# PC-FX.net
KiCad netlist of a schematic drawn in EAGLE
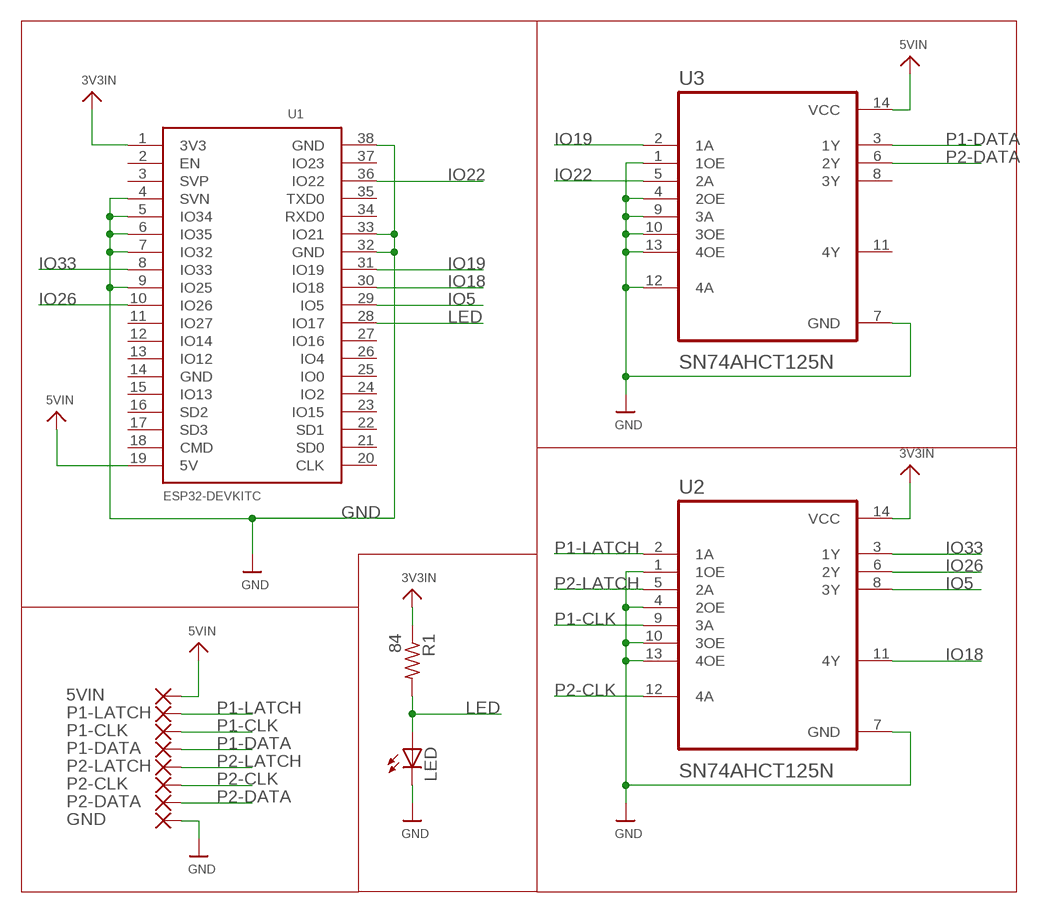
[diagram p0: schematic, sheet 1]

(export (version "E")
  (design (tool "Eeschema 10.0.6"))
  (components
    (comp (ref "5VIN")
      (value "SMD5")
      (footprint "eagle-import:SMD2,54-5,08")
      (libsource (lib "eagle-import") (part "SMD5"))
    )
    (comp (ref "GND")
      (value "SMD5")
      (footprint "eagle-import:SMD2,54-5,08")
      (libsource (lib "eagle-import") (part "SMD5"))
    )
    (comp (ref "LED")
      (value "LEDCHIPLED_1206")
      (footprint "eagle-import:CHIPLED_1206")
      (libsource (lib "eagle-import") (part "LEDCHIPLED_1206"))
    )
    (comp (ref "P1-CLK")
      (value "SMD5")
      (footprint "eagle-import:SMD2,54-5,08")
      (libsource (lib "eagle-import") (part "SMD5"))
    )
    (comp (ref "P1-DATA")
      (value "SMD5")
      (footprint "eagle-import:SMD2,54-5,08")
      (libsource (lib "eagle-import") (part "SMD5"))
    )
    (comp (ref "P1-LATCH")
      (value "SMD5")
      (footprint "eagle-import:SMD2,54-5,08")
      (libsource (lib "eagle-import") (part "SMD5"))
    )
    (comp (ref "P2-CLK")
      (value "SMD5")
      (footprint "eagle-import:SMD2,54-5,08")
      (libsource (lib "eagle-import") (part "SMD5"))
    )
    (comp (ref "P2-DATA")
      (value "SMD5")
      (footprint "eagle-import:SMD2,54-5,08")
      (libsource (lib "eagle-import") (part "SMD5"))
    )
    (comp (ref "P2-LATCH")
      (value "SMD5")
      (footprint "eagle-import:SMD2,54-5,08")
      (libsource (lib "eagle-import") (part "SMD5"))
    )
    (comp (ref "R1")
      (value "84")
      (footprint "eagle-import:R1206")
      (libsource (lib "eagle-import") (part "R-US_R1206"))
    )
    (comp (ref "U1")
      (value "ESP32DEVKITC")
      (footprint "eagle-import:ESP32-DEVKITC")
      (libsource (lib "eagle-import") (part "ESP32DEVKITC"))
    )
    (comp (ref "U2")
      (value "SN74AHCT125N")
      (footprint "eagle-import:DIP794W45P254L1969H508Q14")
      (fields (field (name "MF") "Texas Instruments"))
      (libsource (lib "eagle-import") (part "SN74AHCT125N"))
    )
    (comp (ref "U3")
      (value "SN74AHCT125N")
      (footprint "eagle-import:DIP794W45P254L1969H508Q14")
      (fields (field (name "MF") "Texas Instruments"))
      (libsource (lib "eagle-import") (part "SN74AHCT125N"))
    )
  )
  (nets
    (net (code "1") (name "/IO5") (class "Default")
      (node (ref "U1") (pin "29") (pinfunction "IO5_29") (pintype "bidirectional"))
      (node (ref "U2") (pin "8") (pinfunction "3Y_8") (pintype "output"))
    )
    (net (code "2") (name "/IO18") (class "Default")
      (node (ref "U1") (pin "30") (pinfunction "IO18_30") (pintype "bidirectional"))
      (node (ref "U2") (pin "11") (pinfunction "4Y_11") (pintype "output"))
    )
    (net (code "3") (name "/IO19") (class "Default")
      (node (ref "U1") (pin "31") (pinfunction "IO19_31") (pintype "bidirectional"))
      (node (ref "U3") (pin "2") (pinfunction "1A_2") (pintype "input"))
    )
    (net (code "4") (name "/IO22") (class "Default")
      (node (ref "U1") (pin "36") (pinfunction "IO22_36") (pintype "bidirectional"))
      (node (ref "U3") (pin "5") (pinfunction "2A_5") (pintype "input"))
    )
    (net (code "5") (name "/IO26") (class "Default")
      (node (ref "U1") (pin "10") (pinfunction "IO26_10") (pintype "bidirectional"))
      (node (ref "U2") (pin "6") (pinfunction "2Y_6") (pintype "output"))
    )
    (net (code "6") (name "/IO33") (class "Default")
      (node (ref "U1") (pin "8") (pinfunction "IO33_8") (pintype "bidirectional"))
      (node (ref "U2") (pin "3") (pinfunction "1Y_3") (pintype "output"))
    )
    (net (code "7") (name "/LED") (class "Default")
      (node (ref "LED") (pin "A") (pinfunction "A_A") (pintype "passive"))
      (node (ref "R1") (pin "2") (pinfunction "2_2") (pintype "passive"))
      (node (ref "U1") (pin "28") (pinfunction "IO17_28") (pintype "bidirectional"))
    )
    (net (code "8") (name "/P1-CLK") (class "Default")
      (node (ref "P1-CLK") (pin "1") (pinfunction "P_1") (pintype "passive"))
      (node (ref "U2") (pin "9") (pinfunction "3A_9") (pintype "input"))
    )
    (net (code "9") (name "/P1-DATA") (class "Default")
      (node (ref "P1-DATA") (pin "1") (pinfunction "P_1") (pintype "passive"))
      (node (ref "U3") (pin "3") (pinfunction "1Y_3") (pintype "output"))
    )
    (net (code "10") (name "/P1-LATCH") (class "Default")
      (node (ref "P1-LATCH") (pin "1") (pinfunction "P_1") (pintype "passive"))
      (node (ref "U2") (pin "2") (pinfunction "1A_2") (pintype "input"))
    )
    (net (code "11") (name "/P2-CLK") (class "Default")
      (node (ref "P2-CLK") (pin "1") (pinfunction "P_1") (pintype "passive"))
      (node (ref "U2") (pin "12") (pinfunction "4A_12") (pintype "bidirectional"))
    )
    (net (code "12") (name "/P2-DATA") (class "Default")
      (node (ref "P2-DATA") (pin "1") (pinfunction "P_1") (pintype "passive"))
      (node (ref "U3") (pin "6") (pinfunction "2Y_6") (pintype "output"))
    )
    (net (code "13") (name "/P2-LATCH") (class "Default")
      (node (ref "P2-LATCH") (pin "1") (pinfunction "P_1") (pintype "passive"))
      (node (ref "U2") (pin "5") (pinfunction "2A_5") (pintype "input"))
    )
    (net (code "14") (name "3V3IN") (class "Default")
      (node (ref "R1") (pin "1") (pinfunction "1_1") (pintype "passive"))
      (node (ref "U1") (pin "1") (pinfunction "3V3_1") (pintype "bidirectional"))
      (node (ref "U2") (pin "14") (pinfunction "VCC_14") (pintype "power_in"))
    )
    (net (code "15") (name "5VIN") (class "Default")
      (node (ref "5VIN") (pin "1") (pinfunction "P_1") (pintype "passive"))
      (node (ref "U1") (pin "19") (pinfunction "5V_19") (pintype "bidirectional"))
      (node (ref "U3") (pin "14") (pinfunction "VCC_14") (pintype "power_in"))
    )
    (net (code "16") (name "GND") (class "Default")
      (node (ref "GND") (pin "1") (pinfunction "P_1") (pintype "passive"))
      (node (ref "LED") (pin "C") (pinfunction "C_C") (pintype "passive"))
      (node (ref "U1") (pin "32") (pinfunction "GND_32") (pintype "bidirectional"))
      (node (ref "U1") (pin "33") (pinfunction "IO21_33") (pintype "bidirectional"))
      (node (ref "U1") (pin "38") (pinfunction "GND_38") (pintype "bidirectional"))
      (node (ref "U1") (pin "4") (pinfunction "SVN_4") (pintype "bidirectional"))
      (node (ref "U1") (pin "5") (pinfunction "IO34_5") (pintype "bidirectional"))
      (node (ref "U1") (pin "6") (pinfunction "IO35_6") (pintype "bidirectional"))
      (node (ref "U1") (pin "7") (pinfunction "IO32_7") (pintype "bidirectional"))
      (node (ref "U1") (pin "9") (pinfunction "IO25_9") (pintype "bidirectional"))
      (node (ref "U2") (pin "1") (pinfunction "1OE_1") (pintype "input"))
      (node (ref "U2") (pin "10") (pinfunction "3OE_10") (pintype "input"))
      (node (ref "U2") (pin "13") (pinfunction "4OE_13") (pintype "input"))
      (node (ref "U2") (pin "4") (pinfunction "2OE_4") (pintype "input"))
      (node (ref "U2") (pin "7") (pinfunction "GND_7") (pintype "power_in"))
      (node (ref "U3") (pin "1") (pinfunction "1OE_1") (pintype "input"))
      (node (ref "U3") (pin "10") (pinfunction "3OE_10") (pintype "input"))
      (node (ref "U3") (pin "12") (pinfunction "4A_12") (pintype "bidirectional"))
      (node (ref "U3") (pin "13") (pinfunction "4OE_13") (pintype "input"))
      (node (ref "U3") (pin "4") (pinfunction "2OE_4") (pintype "input"))
      (node (ref "U3") (pin "7") (pinfunction "GND_7") (pintype "power_in"))
      (node (ref "U3") (pin "9") (pinfunction "3A_9") (pintype "input"))
    )
    (net (code "17") (name "unconnected-(U1-CLK-Pad20)") (class "Default")
      (node (ref "U1") (pin "20") (pinfunction "CLK_20") (pintype "bidirectional"))
    )
    (net (code "18") (name "unconnected-(U1-CMD-Pad18)") (class "Default")
      (node (ref "U1") (pin "18") (pinfunction "CMD_18") (pintype "bidirectional"))
    )
    (net (code "19") (name "unconnected-(U1-EN-Pad2)") (class "Default")
      (node (ref "U1") (pin "2") (pinfunction "EN_2") (pintype "bidirectional"))
    )
    (net (code "20") (name "unconnected-(U1-GND-Pad14)") (class "Default")
      (node (ref "U1") (pin "14") (pinfunction "GND_14") (pintype "bidirectional"))
    )
    (net (code "21") (name "unconnected-(U1-IO0-Pad25)") (class "Default")
      (node (ref "U1") (pin "25") (pinfunction "IO0_25") (pintype "bidirectional"))
    )
    (net (code "22") (name "unconnected-(U1-IO2-Pad24)") (class "Default")
      (node (ref "U1") (pin "24") (pinfunction "IO2_24") (pintype "bidirectional"))
    )
    (net (code "23") (name "unconnected-(U1-IO4-Pad26)") (class "Default")
      (node (ref "U1") (pin "26") (pinfunction "IO4_26") (pintype "bidirectional"))
    )
    (net (code "24") (name "unconnected-(U1-IO12-Pad13)") (class "Default")
      (node (ref "U1") (pin "13") (pinfunction "IO12_13") (pintype "bidirectional"))
    )
    (net (code "25") (name "unconnected-(U1-IO13-Pad15)") (class "Default")
      (node (ref "U1") (pin "15") (pinfunction "IO13_15") (pintype "bidirectional"))
    )
    (net (code "26") (name "unconnected-(U1-IO14-Pad12)") (class "Default")
      (node (ref "U1") (pin "12") (pinfunction "IO14_12") (pintype "bidirectional"))
    )
    (net (code "27") (name "unconnected-(U1-IO15-Pad23)") (class "Default")
      (node (ref "U1") (pin "23") (pinfunction "IO15_23") (pintype "bidirectional"))
    )
    (net (code "28") (name "unconnected-(U1-IO16-Pad27)") (class "Default")
      (node (ref "U1") (pin "27") (pinfunction "IO16_27") (pintype "bidirectional"))
    )
    (net (code "29") (name "unconnected-(U1-IO23-Pad37)") (class "Default")
      (node (ref "U1") (pin "37") (pinfunction "IO23_37") (pintype "bidirectional"))
    )
    (net (code "30") (name "unconnected-(U1-IO27-Pad11)") (class "Default")
      (node (ref "U1") (pin "11") (pinfunction "IO27_11") (pintype "bidirectional"))
    )
    (net (code "31") (name "unconnected-(U1-RXD0-Pad34)") (class "Default")
      (node (ref "U1") (pin "34") (pinfunction "RXD0_34") (pintype "bidirectional"))
    )
    (net (code "32") (name "unconnected-(U1-SD0-Pad21)") (class "Default")
      (node (ref "U1") (pin "21") (pinfunction "SD0_21") (pintype "bidirectional"))
    )
    (net (code "33") (name "unconnected-(U1-SD1-Pad22)") (class "Default")
      (node (ref "U1") (pin "22") (pinfunction "SD1_22") (pintype "bidirectional"))
    )
    (net (code "34") (name "unconnected-(U1-SD2-Pad16)") (class "Default")
      (node (ref "U1") (pin "16") (pinfunction "SD2_16") (pintype "bidirectional"))
    )
    (net (code "35") (name "unconnected-(U1-SD3-Pad17)") (class "Default")
      (node (ref "U1") (pin "17") (pinfunction "SD3_17") (pintype "bidirectional"))
    )
    (net (code "36") (name "unconnected-(U1-SVP-Pad3)") (class "Default")
      (node (ref "U1") (pin "3") (pinfunction "SVP_3") (pintype "bidirectional"))
    )
    (net (code "37") (name "unconnected-(U1-TXD0-Pad35)") (class "Default")
      (node (ref "U1") (pin "35") (pinfunction "TXD0_35") (pintype "bidirectional"))
    )
    (net (code "38") (name "unconnected-(U3-3Y-Pad8)") (class "Default")
      (node (ref "U3") (pin "8") (pinfunction "3Y_8") (pintype "output"))
    )
    (net (code "39") (name "unconnected-(U3-4Y-Pad11)") (class "Default")
      (node (ref "U3") (pin "11") (pinfunction "4Y_11") (pintype "output"))
    )
  )
)
